# tsal-illumination.net
KiCad netlist of a schematic drawn in Altium Designer
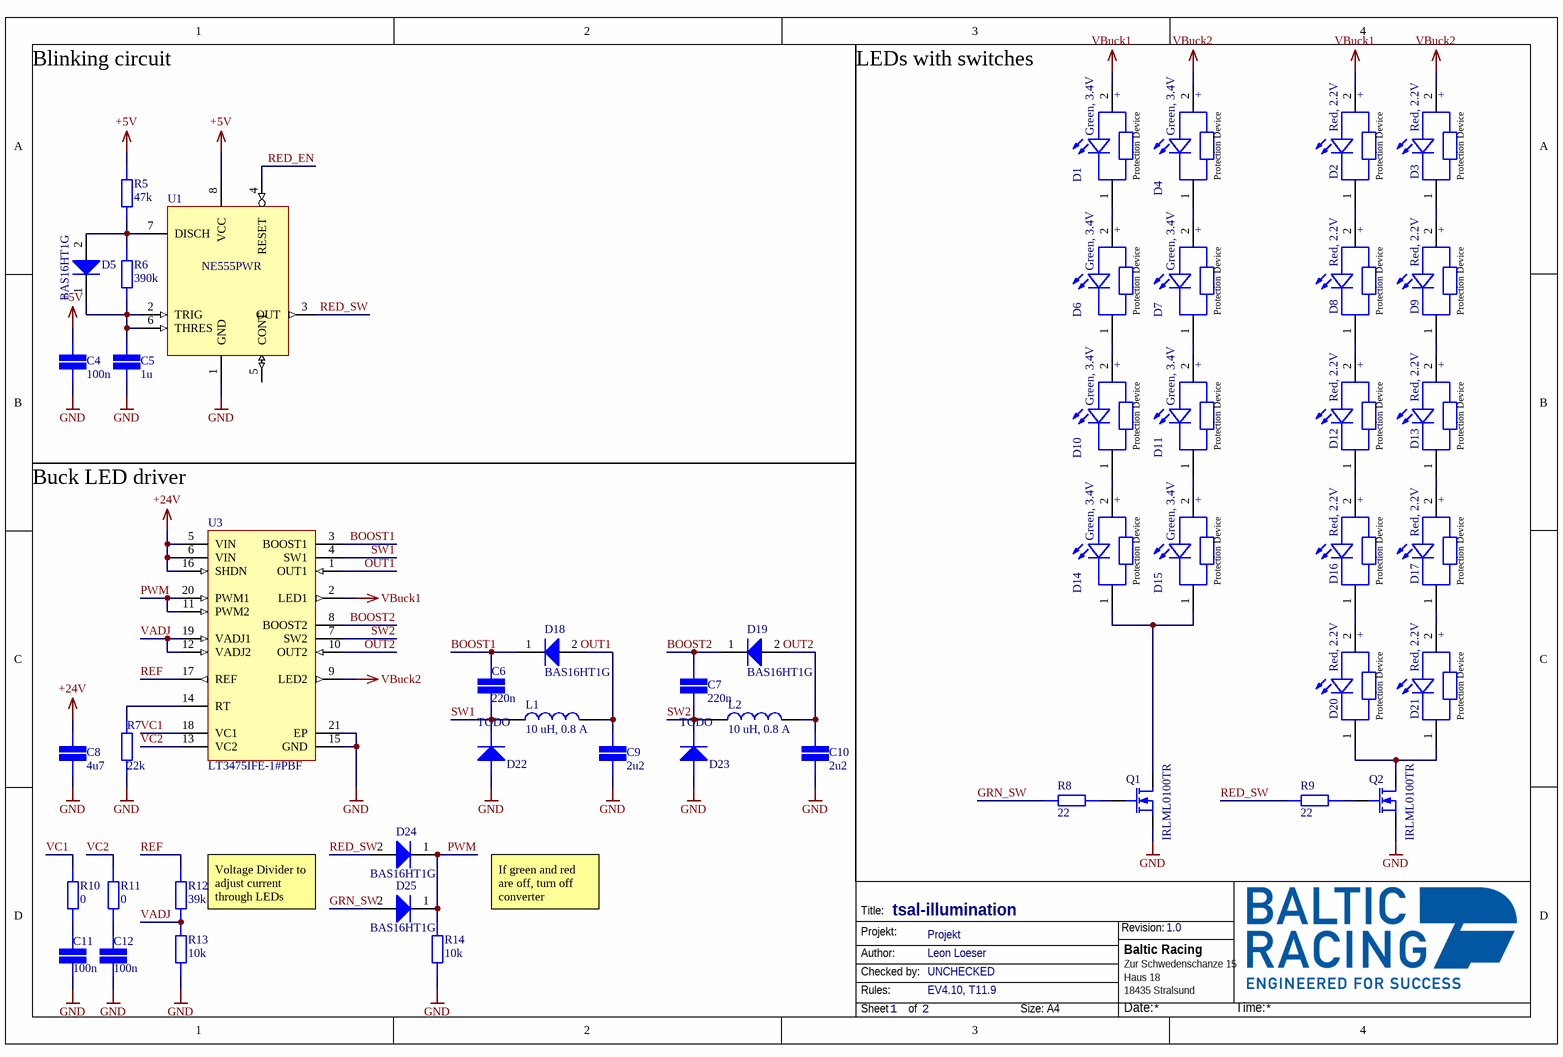
[diagram p0: tsal-illumination.SchDoc]

(export (version "E")
  (design (tool "Eeschema 10.0.6"))
  (components
    (comp (ref "C4")
      (value "100n")
      (footprint "CAP 0603/1608")
      (description "Capacitor with multiple Footprints")
      (fields (field (name "Comment") "SMD Capacitor"))
      (libsource (lib "") (part "SMD Capacitor_1"))
    )
    (comp (ref "C5")
      (value "1u")
      (footprint "CAP 0805/2012")
      (description "Capacitor with multiple Footprints")
      (fields (field (name "Comment") "SMD Capacitor"))
      (libsource (lib "Standardbauteile") (part "SMD Capacitor"))
    )
    (comp (ref "C6")
      (value "220n")
      (footprint "CAP 0603/1608")
      (description "Capacitor with multiple Footprints")
      (fields (field (name "Comment") "SMD Capacitor"))
      (libsource (lib "") (part "SMD Capacitor_1"))
    )
    (comp (ref "C7")
      (value "220n")
      (footprint "CAP 0603/1608")
      (description "Capacitor with multiple Footprints")
      (fields (field (name "Comment") "SMD Capacitor"))
      (libsource (lib "") (part "SMD Capacitor_1"))
    )
    (comp (ref "C8")
      (value "4u7")
      (footprint "CAP 1206/3216")
      (description "Capacitor with multiple Footprints")
      (fields (field (name "Comment") "SMD Capacitor"))
      (libsource (lib "") (part "SMD Capacitor_1"))
    )
    (comp (ref "C9")
      (value "2u2")
      (footprint "CAP 1206/3216")
      (description "Capacitor with multiple Footprints")
      (fields (field (name "Comment") "SMD Capacitor"))
      (libsource (lib "") (part "SMD Capacitor_1"))
    )
    (comp (ref "C10")
      (value "2u2")
      (footprint "CAP 1206/3216")
      (description "Capacitor with multiple Footprints")
      (fields (field (name "Comment") "SMD Capacitor"))
      (libsource (lib "") (part "SMD Capacitor_1"))
    )
    (comp (ref "C11")
      (value "100n")
      (footprint "CAP 0603/1608")
      (description "Capacitor with multiple Footprints")
      (fields (field (name "Comment") "SMD Capacitor"))
      (libsource (lib "") (part "SMD Capacitor_1"))
    )
    (comp (ref "C12")
      (value "100n")
      (footprint "CAP 0603/1608")
      (description "Capacitor with multiple Footprints")
      (fields (field (name "Comment") "SMD Capacitor"))
      (libsource (lib "") (part "SMD Capacitor_1"))
    )
    (comp (ref "D1")
      (value "Green, 3.4V")
      (footprint "WL-SMDC_3535")
      (description "WL-SMDC SMT Mono-color Ceramic LED Waterclear, size 3535, 3.4V, Green")
      (fields
        (field (name "MANUFACTURER PART NUMBER") "150353GS74500")
        (field (name "MANUFACTURER") "Wurth Elektronik")
      )
      (libsource (lib "Altium_WL-SMDC (rev20a)") (part "150353GS74500"))
    )
    (comp (ref "D2")
      (value "Red, 2.2V")
      (footprint "WL-SMDC_3535")
      (description "WL-SMDC SMT Mono-color Ceramic LED Waterclear, size 3535, 2.2V, Red")
      (fields
        (field (name "MANUFACTURER PART NUMBER") "150353RS74500")
        (field (name "MANUFACTURER") "Wurth Elektronik")
      )
      (libsource (lib "Altium_WL-SMDC (rev20a)") (part "150353RS74500"))
    )
    (comp (ref "D3")
      (value "Red, 2.2V")
      (footprint "WL-SMDC_3535")
      (description "WL-SMDC SMT Mono-color Ceramic LED Waterclear, size 3535, 2.2V, Red")
      (fields
        (field (name "MANUFACTURER PART NUMBER") "150353RS74500")
        (field (name "MANUFACTURER") "Wurth Elektronik")
      )
      (libsource (lib "Altium_WL-SMDC (rev20a)") (part "150353RS74500"))
    )
    (comp (ref "D4")
      (value "Green, 3.4V")
      (footprint "WL-SMDC_3535")
      (description "WL-SMDC SMT Mono-color Ceramic LED Waterclear, size 3535, 3.4V, Green")
      (fields
        (field (name "MANUFACTURER PART NUMBER") "150353GS74500")
        (field (name "MANUFACTURER") "Wurth Elektronik")
      )
      (libsource (lib "Altium_WL-SMDC (rev20a)") (part "150353GS74500"))
    )
    (comp (ref "D5")
      (value "BAS16HT1G")
      (footprint "ONSC-SOD-323-2-477-02_V")
      (description "Switching Diode, 2-Pin SOD-323, Pb-Free, Tape and Reel")
      (fields (field (name "MANUFACTURER") "On Semiconductor"))
      (libsource (lib "Altium Content Vault") (part "ONSC-D-K1A2-2"))
    )
    (comp (ref "D6")
      (value "Green, 3.4V")
      (footprint "WL-SMDC_3535")
      (description "WL-SMDC SMT Mono-color Ceramic LED Waterclear, size 3535, 3.4V, Green")
      (fields
        (field (name "MANUFACTURER PART NUMBER") "150353GS74500")
        (field (name "MANUFACTURER") "Wurth Elektronik")
      )
      (libsource (lib "Altium_WL-SMDC (rev20a)") (part "150353GS74500"))
    )
    (comp (ref "D7")
      (value "Green, 3.4V")
      (footprint "WL-SMDC_3535")
      (description "WL-SMDC SMT Mono-color Ceramic LED Waterclear, size 3535, 3.4V, Green")
      (fields
        (field (name "MANUFACTURER PART NUMBER") "150353GS74500")
        (field (name "MANUFACTURER") "Wurth Elektronik")
      )
      (libsource (lib "Altium_WL-SMDC (rev20a)") (part "150353GS74500"))
    )
    (comp (ref "D8")
      (value "Red, 2.2V")
      (footprint "WL-SMDC_3535")
      (description "WL-SMDC SMT Mono-color Ceramic LED Waterclear, size 3535, 2.2V, Red")
      (fields
        (field (name "MANUFACTURER PART NUMBER") "150353RS74500")
        (field (name "MANUFACTURER") "Wurth Elektronik")
      )
      (libsource (lib "Altium_WL-SMDC (rev20a)") (part "150353RS74500"))
    )
    (comp (ref "D9")
      (value "Red, 2.2V")
      (footprint "WL-SMDC_3535")
      (description "WL-SMDC SMT Mono-color Ceramic LED Waterclear, size 3535, 2.2V, Red")
      (fields
        (field (name "MANUFACTURER PART NUMBER") "150353RS74500")
        (field (name "MANUFACTURER") "Wurth Elektronik")
      )
      (libsource (lib "Altium_WL-SMDC (rev20a)") (part "150353RS74500"))
    )
    (comp (ref "D10")
      (value "Green, 3.4V")
      (footprint "WL-SMDC_3535")
      (description "WL-SMDC SMT Mono-color Ceramic LED Waterclear, size 3535, 3.4V, Green")
      (fields
        (field (name "MANUFACTURER PART NUMBER") "150353GS74500")
        (field (name "MANUFACTURER") "Wurth Elektronik")
      )
      (libsource (lib "Altium_WL-SMDC (rev20a)") (part "150353GS74500"))
    )
    (comp (ref "D11")
      (value "Green, 3.4V")
      (footprint "WL-SMDC_3535")
      (description "WL-SMDC SMT Mono-color Ceramic LED Waterclear, size 3535, 3.4V, Green")
      (fields
        (field (name "MANUFACTURER PART NUMBER") "150353GS74500")
        (field (name "MANUFACTURER") "Wurth Elektronik")
      )
      (libsource (lib "Altium_WL-SMDC (rev20a)") (part "150353GS74500"))
    )
    (comp (ref "D12")
      (value "Red, 2.2V")
      (footprint "WL-SMDC_3535")
      (description "WL-SMDC SMT Mono-color Ceramic LED Waterclear, size 3535, 2.2V, Red")
      (fields
        (field (name "MANUFACTURER PART NUMBER") "150353RS74500")
        (field (name "MANUFACTURER") "Wurth Elektronik")
      )
      (libsource (lib "Altium_WL-SMDC (rev20a)") (part "150353RS74500"))
    )
    (comp (ref "D13")
      (value "Red, 2.2V")
      (footprint "WL-SMDC_3535")
      (description "WL-SMDC SMT Mono-color Ceramic LED Waterclear, size 3535, 2.2V, Red")
      (fields
        (field (name "MANUFACTURER PART NUMBER") "150353RS74500")
        (field (name "MANUFACTURER") "Wurth Elektronik")
      )
      (libsource (lib "Altium_WL-SMDC (rev20a)") (part "150353RS74500"))
    )
    (comp (ref "D14")
      (value "Green, 3.4V")
      (footprint "WL-SMDC_3535")
      (description "WL-SMDC SMT Mono-color Ceramic LED Waterclear, size 3535, 3.4V, Green")
      (fields
        (field (name "MANUFACTURER PART NUMBER") "150353GS74500")
        (field (name "MANUFACTURER") "Wurth Elektronik")
      )
      (libsource (lib "Altium_WL-SMDC (rev20a)") (part "150353GS74500"))
    )
    (comp (ref "D15")
      (value "Green, 3.4V")
      (footprint "WL-SMDC_3535")
      (description "WL-SMDC SMT Mono-color Ceramic LED Waterclear, size 3535, 3.4V, Green")
      (fields
        (field (name "MANUFACTURER PART NUMBER") "150353GS74500")
        (field (name "MANUFACTURER") "Wurth Elektronik")
      )
      (libsource (lib "Altium_WL-SMDC (rev20a)") (part "150353GS74500"))
    )
    (comp (ref "D16")
      (value "Red, 2.2V")
      (footprint "WL-SMDC_3535")
      (description "WL-SMDC SMT Mono-color Ceramic LED Waterclear, size 3535, 2.2V, Red")
      (fields
        (field (name "MANUFACTURER PART NUMBER") "150353RS74500")
        (field (name "MANUFACTURER") "Wurth Elektronik")
      )
      (libsource (lib "Altium_WL-SMDC (rev20a)") (part "150353RS74500"))
    )
    (comp (ref "D17")
      (value "Red, 2.2V")
      (footprint "WL-SMDC_3535")
      (description "WL-SMDC SMT Mono-color Ceramic LED Waterclear, size 3535, 2.2V, Red")
      (fields
        (field (name "MANUFACTURER PART NUMBER") "150353RS74500")
        (field (name "MANUFACTURER") "Wurth Elektronik")
      )
      (libsource (lib "Altium_WL-SMDC (rev20a)") (part "150353RS74500"))
    )
    (comp (ref "D18")
      (value "BAS16HT1G")
      (footprint "ONSC-SOD-323-2-477-02_V")
      (description "Switching Diode, 2-Pin SOD-323, Pb-Free, Tape and Reel")
      (fields (field (name "MANUFACTURER") "On Semiconductor"))
      (libsource (lib "Altium Content Vault") (part "ONSC-D-K1A2-2"))
    )
    (comp (ref "D19")
      (value "BAS16HT1G")
      (footprint "ONSC-SOD-323-2-477-02_V")
      (description "Switching Diode, 2-Pin SOD-323, Pb-Free, Tape and Reel")
      (fields (field (name "MANUFACTURER") "On Semiconductor"))
      (libsource (lib "Altium Content Vault") (part "ONSC-D-K1A2-2"))
    )
    (comp (ref "D20")
      (value "Red, 2.2V")
      (footprint "WL-SMDC_3535")
      (description "WL-SMDC SMT Mono-color Ceramic LED Waterclear, size 3535, 2.2V, Red")
      (fields
        (field (name "MANUFACTURER PART NUMBER") "150353RS74500")
        (field (name "MANUFACTURER") "Wurth Elektronik")
      )
      (libsource (lib "Altium_WL-SMDC (rev20a)") (part "150353RS74500"))
    )
    (comp (ref "D21")
      (value "Red, 2.2V")
      (footprint "WL-SMDC_3535")
      (description "WL-SMDC SMT Mono-color Ceramic LED Waterclear, size 3535, 2.2V, Red")
      (fields
        (field (name "MANUFACTURER PART NUMBER") "150353RS74500")
        (field (name "MANUFACTURER") "Wurth Elektronik")
      )
      (libsource (lib "Altium_WL-SMDC (rev20a)") (part "150353RS74500"))
    )
    (comp (ref "D22")
      (value "TODO")
      (footprint "SOD123F")
      (libsource (lib "Standardbauteile") (part "SMD Diode"))
    )
    (comp (ref "D23")
      (value "TODO")
      (footprint "SOD123F")
      (libsource (lib "Standardbauteile") (part "SMD Diode"))
    )
    (comp (ref "D24")
      (value "BAS16HT1G")
      (footprint "ONSC-SOD-323-2-477-02_V")
      (description "Switching Diode, 2-Pin SOD-323, Pb-Free, Tape and Reel")
      (fields (field (name "MANUFACTURER") "On Semiconductor"))
      (libsource (lib "Altium Content Vault") (part "ONSC-D-K1A2-2"))
    )
    (comp (ref "D25")
      (value "BAS16HT1G")
      (footprint "ONSC-SOD-323-2-477-02_V")
      (description "Switching Diode, 2-Pin SOD-323, Pb-Free, Tape and Reel")
      (fields (field (name "MANUFACTURER") "On Semiconductor"))
      (libsource (lib "Altium Content Vault") (part "ONSC-D-K1A2-2"))
    )
    (comp (ref "L1")
      (value "10 uH, 0.8 A")
      (footprint "WE-LQSH_2512")
      (description "SMT Semi-Shielded High Saturation Power Inductor WE-LQSH, size 2512, 10 uH, 0.8 A")
      (fields (field (name "PART NUMBER") "74405024100") (field (name "PUBLISHER") "Wurth Elektronik"))
      (libsource (lib "ALTIUM-WE-LQSH-rev18a") (part "74405024100"))
    )
    (comp (ref "L2")
      (value "10 uH, 0.8 A")
      (footprint "WE-LQSH_2512")
      (description "SMT Semi-Shielded High Saturation Power Inductor WE-LQSH, size 2512, 10 uH, 0.8 A")
      (fields (field (name "PART NUMBER") "74405024100") (field (name "PUBLISHER") "Wurth Elektronik"))
      (libsource (lib "ALTIUM-WE-LQSH-rev18a") (part "74405024100"))
    )
    (comp (ref "Q1")
      (value "IRLML0100TR")
      (footprint "SOT23")
      (description "N-Channel MOSFET")
      (libsource (lib "Standardbauteile") (part "MOSFET N"))
    )
    (comp (ref "Q2")
      (value "IRLML0100TR")
      (footprint "SOT23")
      (description "N-Channel MOSFET")
      (libsource (lib "Standardbauteile") (part "MOSFET N"))
    )
    (comp (ref "R5")
      (value "47k")
      (footprint "STACKPOLE CSR0603")
      (description "Resistor with multiple footprints")
      (fields (field (name "Comment") "SMD Resistor"))
      (libsource (lib "Standardbauteile") (part "SMD Resistor"))
    )
    (comp (ref "R6")
      (value "390k")
      (footprint "STACKPOLE CSR0603")
      (description "Resistor with multiple footprints")
      (fields (field (name "Comment") "SMD Resistor"))
      (libsource (lib "Standardbauteile") (part "SMD Resistor"))
    )
    (comp (ref "R7")
      (value "22k")
      (footprint "STACKPOLE CSR0603")
      (description "Resistor with multiple footprints")
      (fields (field (name "Comment") "SMD Resistor"))
      (libsource (lib "Standardbauteile") (part "SMD Resistor"))
    )
    (comp (ref "R8")
      (value "22")
      (footprint "STACKPOLE CSR0603")
      (description "Resistor with multiple footprints")
      (fields (field (name "Comment") "SMD Resistor"))
      (libsource (lib "Standardbauteile") (part "SMD Resistor"))
    )
    (comp (ref "R9")
      (value "22")
      (footprint "STACKPOLE CSR0603")
      (description "Resistor with multiple footprints")
      (fields (field (name "Comment") "SMD Resistor"))
      (libsource (lib "Standardbauteile") (part "SMD Resistor"))
    )
    (comp (ref "R10")
      (value "0")
      (footprint "STACKPOLE CSR0603")
      (description "Resistor with multiple footprints")
      (fields (field (name "Comment") "SMD Resistor"))
      (libsource (lib "Standardbauteile") (part "SMD Resistor"))
    )
    (comp (ref "R11")
      (value "0")
      (footprint "STACKPOLE CSR0603")
      (description "Resistor with multiple footprints")
      (fields (field (name "Comment") "SMD Resistor"))
      (libsource (lib "Standardbauteile") (part "SMD Resistor"))
    )
    (comp (ref "R12")
      (value "39k")
      (footprint "STACKPOLE CSR0603")
      (description "Resistor with multiple footprints")
      (fields (field (name "Comment") "SMD Resistor"))
      (libsource (lib "Standardbauteile") (part "SMD Resistor"))
    )
    (comp (ref "R13")
      (value "10k")
      (footprint "STACKPOLE CSR0603")
      (description "Resistor with multiple footprints")
      (fields (field (name "Comment") "SMD Resistor"))
      (libsource (lib "Standardbauteile") (part "SMD Resistor"))
    )
    (comp (ref "R14")
      (value "10k")
      (footprint "STACKPOLE CSR0603")
      (description "Resistor with multiple footprints")
      (fields (field (name "Comment") "SMD Resistor"))
      (libsource (lib "Standardbauteile") (part "SMD Resistor"))
    )
    (comp (ref "U1")
      (value "NE555PWR")
      (footprint "8-TSSOP")
      (libsource (lib "Standardbauteile") (part "NE555"))
    )
    (comp (ref "U3")
      (value "LT3475IFE-1#PBF")
      (footprint "LT-FE-20-EPV-CB_L")
      (fields (field (name "MANUFACTURER") "Linear Technology"))
      (libsource (lib "Altium Content Vault") (part "LT-LT3475-X-FE-20"))
    )
  )
  (nets
    (net (code "1") (name "+5V") (class "Default")
      (node (ref "C4") (pin "2") (pinfunction "2_2") (pintype "passive"))
      (node (ref "R5") (pin "2") (pinfunction "2_2") (pintype "passive"))
      (node (ref "U1") (pin "8") (pinfunction "VCC_8") (pintype "power_in"))
    )
    (net (code "2") (name "+24V") (class "Default")
      (node (ref "C8") (pin "2") (pinfunction "2_2") (pintype "passive"))
      (node (ref "U3") (pin "16") (pinfunction "SHDN_16") (pintype "input"))
      (node (ref "U3") (pin "5") (pinfunction "VIN_5") (pintype "power_in"))
      (node (ref "U3") (pin "6") (pinfunction "VIN_6") (pintype "power_in"))
    )
    (net (code "3") (name "/BOOST1") (class "Default")
      (node (ref "C6") (pin "2") (pinfunction "2_2") (pintype "passive"))
      (node (ref "D18") (pin "1") (pinfunction "K_1") (pintype "passive"))
      (node (ref "U3") (pin "3") (pinfunction "BOOST1_3") (pintype "passive"))
    )
    (net (code "4") (name "/BOOST2") (class "Default")
      (node (ref "C7") (pin "2") (pinfunction "2_2") (pintype "passive"))
      (node (ref "D19") (pin "1") (pinfunction "K_1") (pintype "passive"))
      (node (ref "U3") (pin "8") (pinfunction "BOOST2_8") (pintype "passive"))
    )
    (net (code "5") (name "/GRN_SW") (class "Default")
      (node (ref "D25") (pin "2") (pinfunction "A_2") (pintype "passive"))
      (node (ref "R8") (pin "2") (pinfunction "2_2") (pintype "passive"))
    )
    (net (code "6") (name "/OUT1") (class "Default")
      (node (ref "C9") (pin "2") (pinfunction "2_2") (pintype "passive"))
      (node (ref "D18") (pin "2") (pinfunction "A_2") (pintype "passive"))
      (node (ref "L1") (pin "2") (pinfunction "2_2") (pintype "passive"))
      (node (ref "U3") (pin "1") (pinfunction "OUT1_1") (pintype "input"))
    )
    (net (code "7") (name "/OUT2") (class "Default")
      (node (ref "C10") (pin "2") (pinfunction "2_2") (pintype "passive"))
      (node (ref "D19") (pin "2") (pinfunction "A_2") (pintype "passive"))
      (node (ref "L2") (pin "2") (pinfunction "2_2") (pintype "passive"))
      (node (ref "U3") (pin "10") (pinfunction "OUT2_10") (pintype "input"))
    )
    (net (code "8") (name "/PWM") (class "Default")
      (node (ref "D24") (pin "1") (pinfunction "K_1") (pintype "passive"))
      (node (ref "D25") (pin "1") (pinfunction "K_1") (pintype "passive"))
      (node (ref "R14") (pin "1") (pinfunction "1_1") (pintype "passive"))
      (node (ref "U3") (pin "11") (pinfunction "PWM2_11") (pintype "input"))
      (node (ref "U3") (pin "20") (pinfunction "PWM1_20") (pintype "input"))
    )
    (net (code "9") (name "/RED_EN") (class "Default")
      (node (ref "U1") (pin "4") (pinfunction "RESET_4") (pintype "input"))
    )
    (net (code "10") (name "/RED_SW") (class "Default")
      (node (ref "D24") (pin "2") (pinfunction "A_2") (pintype "passive"))
      (node (ref "R9") (pin "2") (pinfunction "2_2") (pintype "passive"))
      (node (ref "U1") (pin "3") (pinfunction "OUT_3") (pintype "output"))
    )
    (net (code "11") (name "/REF") (class "Default")
      (node (ref "R12") (pin "1") (pinfunction "1_1") (pintype "passive"))
      (node (ref "U3") (pin "17") (pinfunction "REF_17") (pintype "output"))
    )
    (net (code "12") (name "/SW1") (class "Default")
      (node (ref "C6") (pin "1") (pinfunction "1_1") (pintype "passive"))
      (node (ref "D22") (pin "C") (pinfunction "C_C") (pintype "passive"))
      (node (ref "L1") (pin "1") (pinfunction "1_1") (pintype "passive"))
      (node (ref "U3") (pin "4") (pinfunction "SW1_4") (pintype "passive"))
    )
    (net (code "13") (name "/SW2") (class "Default")
      (node (ref "C7") (pin "1") (pinfunction "1_1") (pintype "passive"))
      (node (ref "D23") (pin "C") (pinfunction "C_C") (pintype "passive"))
      (node (ref "L2") (pin "1") (pinfunction "1_1") (pintype "passive"))
      (node (ref "U3") (pin "7") (pinfunction "SW2_7") (pintype "passive"))
    )
    (net (code "14") (name "/VADJ") (class "Default")
      (node (ref "R12") (pin "2") (pinfunction "2_2") (pintype "passive"))
      (node (ref "R13") (pin "1") (pinfunction "1_1") (pintype "passive"))
      (node (ref "U3") (pin "12") (pinfunction "VADJ2_12") (pintype "input"))
      (node (ref "U3") (pin "19") (pinfunction "VADJ1_19") (pintype "input"))
    )
    (net (code "15") (name "/VC1") (class "Default")
      (node (ref "R10") (pin "1") (pinfunction "1_1") (pintype "passive"))
      (node (ref "U3") (pin "18") (pinfunction "VC1_18") (pintype "passive"))
    )
    (net (code "16") (name "/VC2") (class "Default")
      (node (ref "R11") (pin "1") (pinfunction "1_1") (pintype "passive"))
      (node (ref "U3") (pin "13") (pinfunction "VC2_13") (pintype "passive"))
    )
    (net (code "17") (name "GND") (class "Default")
      (node (ref "C10") (pin "1") (pinfunction "1_1") (pintype "passive"))
      (node (ref "C11") (pin "1") (pinfunction "1_1") (pintype "passive"))
      (node (ref "C12") (pin "1") (pinfunction "1_1") (pintype "passive"))
      (node (ref "C4") (pin "1") (pinfunction "1_1") (pintype "passive"))
      (node (ref "C5") (pin "2") (pinfunction "2_2") (pintype "passive"))
      (node (ref "C8") (pin "1") (pinfunction "1_1") (pintype "passive"))
      (node (ref "C9") (pin "1") (pinfunction "1_1") (pintype "passive"))
      (node (ref "D22") (pin "A") (pinfunction "A_A") (pintype "passive"))
      (node (ref "D23") (pin "A") (pinfunction "A_A") (pintype "passive"))
      (node (ref "Q1") (pin "2") (pinfunction "S_2") (pintype "passive"))
      (node (ref "Q2") (pin "2") (pinfunction "S_2") (pintype "passive"))
      (node (ref "R13") (pin "2") (pinfunction "2_2") (pintype "passive"))
      (node (ref "R14") (pin "2") (pinfunction "2_2") (pintype "passive"))
      (node (ref "R7") (pin "2") (pinfunction "2_2") (pintype "passive"))
      (node (ref "U1") (pin "1") (pinfunction "GND_1") (pintype "power_in"))
      (node (ref "U3") (pin "15") (pinfunction "GND_15") (pintype "power_in"))
      (node (ref "U3") (pin "21") (pinfunction "EP_21") (pintype "power_in"))
    )
    (net (code "18") (name "Net-(C11-Pad2)") (class "Default")
      (node (ref "C11") (pin "2") (pinfunction "2_2") (pintype "passive"))
      (node (ref "R10") (pin "2") (pinfunction "2_2") (pintype "passive"))
    )
    (net (code "19") (name "Net-(C12-Pad2)") (class "Default")
      (node (ref "C12") (pin "2") (pinfunction "2_2") (pintype "passive"))
      (node (ref "R11") (pin "2") (pinfunction "2_2") (pintype "passive"))
    )
    (net (code "20") (name "Net-(D1-K)") (class "Default")
      (node (ref "D1") (pin "1") (pinfunction "K_1") (pintype "passive"))
      (node (ref "D6") (pin "2") (pinfunction "A_2") (pintype "passive"))
    )
    (net (code "21") (name "Net-(D2-K)") (class "Default")
      (node (ref "D2") (pin "1") (pinfunction "K_1") (pintype "passive"))
      (node (ref "D8") (pin "2") (pinfunction "A_2") (pintype "passive"))
    )
    (net (code "22") (name "Net-(D3-K)") (class "Default")
      (node (ref "D3") (pin "1") (pinfunction "K_1") (pintype "passive"))
      (node (ref "D9") (pin "2") (pinfunction "A_2") (pintype "passive"))
    )
    (net (code "23") (name "Net-(D4-K)") (class "Default")
      (node (ref "D4") (pin "1") (pinfunction "K_1") (pintype "passive"))
      (node (ref "D7") (pin "2") (pinfunction "A_2") (pintype "passive"))
    )
    (net (code "24") (name "Net-(D5-A)") (class "Default")
      (node (ref "D5") (pin "2") (pinfunction "A_2") (pintype "passive"))
      (node (ref "R5") (pin "1") (pinfunction "1_1") (pintype "passive"))
      (node (ref "R6") (pin "2") (pinfunction "2_2") (pintype "passive"))
      (node (ref "U1") (pin "7") (pinfunction "DISCH_7") (pintype "open_collector"))
    )
    (net (code "25") (name "Net-(D5-K)") (class "Default")
      (node (ref "C5") (pin "1") (pinfunction "1_1") (pintype "passive"))
      (node (ref "D5") (pin "1") (pinfunction "K_1") (pintype "passive"))
      (node (ref "R6") (pin "1") (pinfunction "1_1") (pintype "passive"))
      (node (ref "U1") (pin "2") (pinfunction "TRIG_2") (pintype "input"))
      (node (ref "U1") (pin "6") (pinfunction "THRES_6") (pintype "input"))
    )
    (net (code "26") (name "Net-(D10-A)") (class "Default")
      (node (ref "D10") (pin "2") (pinfunction "A_2") (pintype "passive"))
      (node (ref "D6") (pin "1") (pinfunction "K_1") (pintype "passive"))
    )
    (net (code "27") (name "Net-(D10-K)") (class "Default")
      (node (ref "D10") (pin "1") (pinfunction "K_1") (pintype "passive"))
      (node (ref "D14") (pin "2") (pinfunction "A_2") (pintype "passive"))
    )
    (net (code "28") (name "Net-(D11-A)") (class "Default")
      (node (ref "D11") (pin "2") (pinfunction "A_2") (pintype "passive"))
      (node (ref "D7") (pin "1") (pinfunction "K_1") (pintype "passive"))
    )
    (net (code "29") (name "Net-(D11-K)") (class "Default")
      (node (ref "D11") (pin "1") (pinfunction "K_1") (pintype "passive"))
      (node (ref "D15") (pin "2") (pinfunction "A_2") (pintype "passive"))
    )
    (net (code "30") (name "Net-(D12-A)") (class "Default")
      (node (ref "D12") (pin "2") (pinfunction "A_2") (pintype "passive"))
      (node (ref "D8") (pin "1") (pinfunction "K_1") (pintype "passive"))
    )
    (net (code "31") (name "Net-(D12-K)") (class "Default")
      (node (ref "D12") (pin "1") (pinfunction "K_1") (pintype "passive"))
      (node (ref "D16") (pin "2") (pinfunction "A_2") (pintype "passive"))
    )
    (net (code "32") (name "Net-(D13-A)") (class "Default")
      (node (ref "D13") (pin "2") (pinfunction "A_2") (pintype "passive"))
      (node (ref "D9") (pin "1") (pinfunction "K_1") (pintype "passive"))
    )
    (net (code "33") (name "Net-(D13-K)") (class "Default")
      (node (ref "D13") (pin "1") (pinfunction "K_1") (pintype "passive"))
      (node (ref "D17") (pin "2") (pinfunction "A_2") (pintype "passive"))
    )
    (net (code "34") (name "Net-(D14-K)") (class "Default")
      (node (ref "D14") (pin "1") (pinfunction "K_1") (pintype "passive"))
      (node (ref "D15") (pin "1") (pinfunction "K_1") (pintype "passive"))
      (node (ref "Q1") (pin "3") (pinfunction "D_3") (pintype "passive"))
    )
    (net (code "35") (name "Net-(D16-K)") (class "Default")
      (node (ref "D16") (pin "1") (pinfunction "K_1") (pintype "passive"))
      (node (ref "D20") (pin "2") (pinfunction "A_2") (pintype "passive"))
    )
    (net (code "36") (name "Net-(D17-K)") (class "Default")
      (node (ref "D17") (pin "1") (pinfunction "K_1") (pintype "passive"))
      (node (ref "D21") (pin "2") (pinfunction "A_2") (pintype "passive"))
    )
    (net (code "37") (name "Net-(D20-K)") (class "Default")
      (node (ref "D20") (pin "1") (pinfunction "K_1") (pintype "passive"))
      (node (ref "D21") (pin "1") (pinfunction "K_1") (pintype "passive"))
      (node (ref "Q2") (pin "3") (pinfunction "D_3") (pintype "passive"))
    )
    (net (code "38") (name "Net-(Q1-G)") (class "Default")
      (node (ref "Q1") (pin "1") (pinfunction "G_1") (pintype "passive"))
      (node (ref "R8") (pin "1") (pinfunction "1_1") (pintype "passive"))
    )
    (net (code "39") (name "Net-(Q2-G)") (class "Default")
      (node (ref "Q2") (pin "1") (pinfunction "G_1") (pintype "passive"))
      (node (ref "R9") (pin "1") (pinfunction "1_1") (pintype "passive"))
    )
    (net (code "40") (name "Net-(U3-RT)") (class "Default")
      (node (ref "R7") (pin "1") (pinfunction "1_1") (pintype "passive"))
      (node (ref "U3") (pin "14") (pinfunction "RT_14") (pintype "passive"))
    )
    (net (code "41") (name "VBuck1") (class "Default")
      (node (ref "D1") (pin "2") (pinfunction "A_2") (pintype "passive"))
      (node (ref "D2") (pin "2") (pinfunction "A_2") (pintype "passive"))
      (node (ref "U3") (pin "2") (pinfunction "LED1_2") (pintype "output"))
    )
    (net (code "42") (name "VBuck2") (class "Default")
      (node (ref "D3") (pin "2") (pinfunction "A_2") (pintype "passive"))
      (node (ref "D4") (pin "2") (pinfunction "A_2") (pintype "passive"))
      (node (ref "U3") (pin "9") (pinfunction "LED2_9") (pintype "output"))
    )
    (net (code "43") (name "unconnected-(U1-CONT-Pad5)") (class "Default")
      (node (ref "U1") (pin "5") (pinfunction "CONT_5") (pintype "bidirectional"))
    )
  )
)
